# Buzzer.net
KiCad netlist of a schematic drawn in Altium Designer
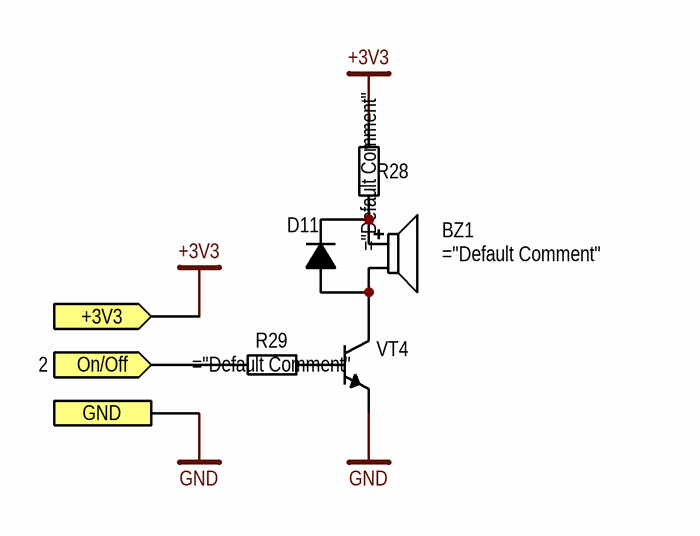
[diagram p0: Buzzer.SchDoc]

(export (version "E")
  (design (tool "Eeschema 10.0.6"))
  (components
    (comp (ref "BZ1")
      (value "~")
      (description "BUZZER MAGNETIC 3V 5X5MM SMD")
      (fields (field (name "TOLERANCE") "* %") (field (name "MANUFACTURER") "PUI Audio, Inc."))
      (libsource (lib "femtoino") (part "SMT-0540-S-R"))
    )
    (comp (ref "D11")
      (value "~")
      (description "DIODE GEN PURP 75V 150MA SOD323")
      (fields (field (name "TOLERANCE") "* %") (field (name "MANUFACTURER") "Micro Commercial Co"))
      (libsource (lib "femtoino") (part "1N4148WX-TP"))
    )
    (comp (ref "R28")
      (value "~")
      (description "RES 22 OHM 1% 1/10W 0603")
      (fields (field (name "TOLERANCE") "1 %") (field (name "MANUFACTURER") "YAGEO"))
      (libsource (lib "femtoino") (part "RC0603FR-0722RL"))
    )
    (comp (ref "R29")
      (value "~")
      (description "RES 1K OHM 1% 1/10W 0603")
      (fields (field (name "TOLERANCE") "1 %") (field (name "MANUFACTURER") "YAGEO"))
      (libsource (lib "femtoino") (part "RC0603FR-071KL"))
    )
    (comp (ref "VT4")
      (value "~")
      (description "TRANS NPN 40V 0.6A SOT23")
      (fields (field (name "TOLERANCE") "* %") (field (name "MANUFACTURER") "Micro Commercial Co"))
      (libsource (lib "femtoino") (part "MMBT2222A-TP"))
    )
  )
  (nets
    (net (code "1") (name "+3V3") (class "Default")
      (node (ref "R28") (pin "2") (pinfunction "2_2") (pintype "passive"))
    )
    (net (code "2") (name "/On{slash}Off") (class "Default")
      (node (ref "R29") (pin "1") (pinfunction "1_1") (pintype "passive"))
    )
    (net (code "3") (name "GND") (class "Default")
      (node (ref "VT4") (pin "E") (pinfunction "E_E") (pintype "passive"))
    )
    (net (code "4") (name "Net-(BZ1-PadNEG)") (class "Default")
      (node (ref "BZ1") (pin "NEG") (pinfunction "NEG_NEG") (pintype "passive"))
      (node (ref "D11") (pin "A") (pinfunction "A_A") (pintype "passive"))
      (node (ref "VT4") (pin "C") (pinfunction "C_C") (pintype "passive"))
    )
    (net (code "5") (name "Net-(BZ1-PadPOS)") (class "Default")
      (node (ref "BZ1") (pin "POS") (pinfunction "POS_POS") (pintype "passive"))
      (node (ref "D11") (pin "C") (pinfunction "C_C") (pintype "passive"))
      (node (ref "R28") (pin "1") (pinfunction "1_1") (pintype "passive"))
    )
    (net (code "6") (name "Net-(R29-Pad2)") (class "Default")
      (node (ref "R29") (pin "2") (pinfunction "2_2") (pintype "passive"))
      (node (ref "VT4") (pin "B") (pinfunction "B_B") (pintype "passive"))
    )
  )
)
